# power.net
KiCad netlist of a schematic drawn in Altium Designer
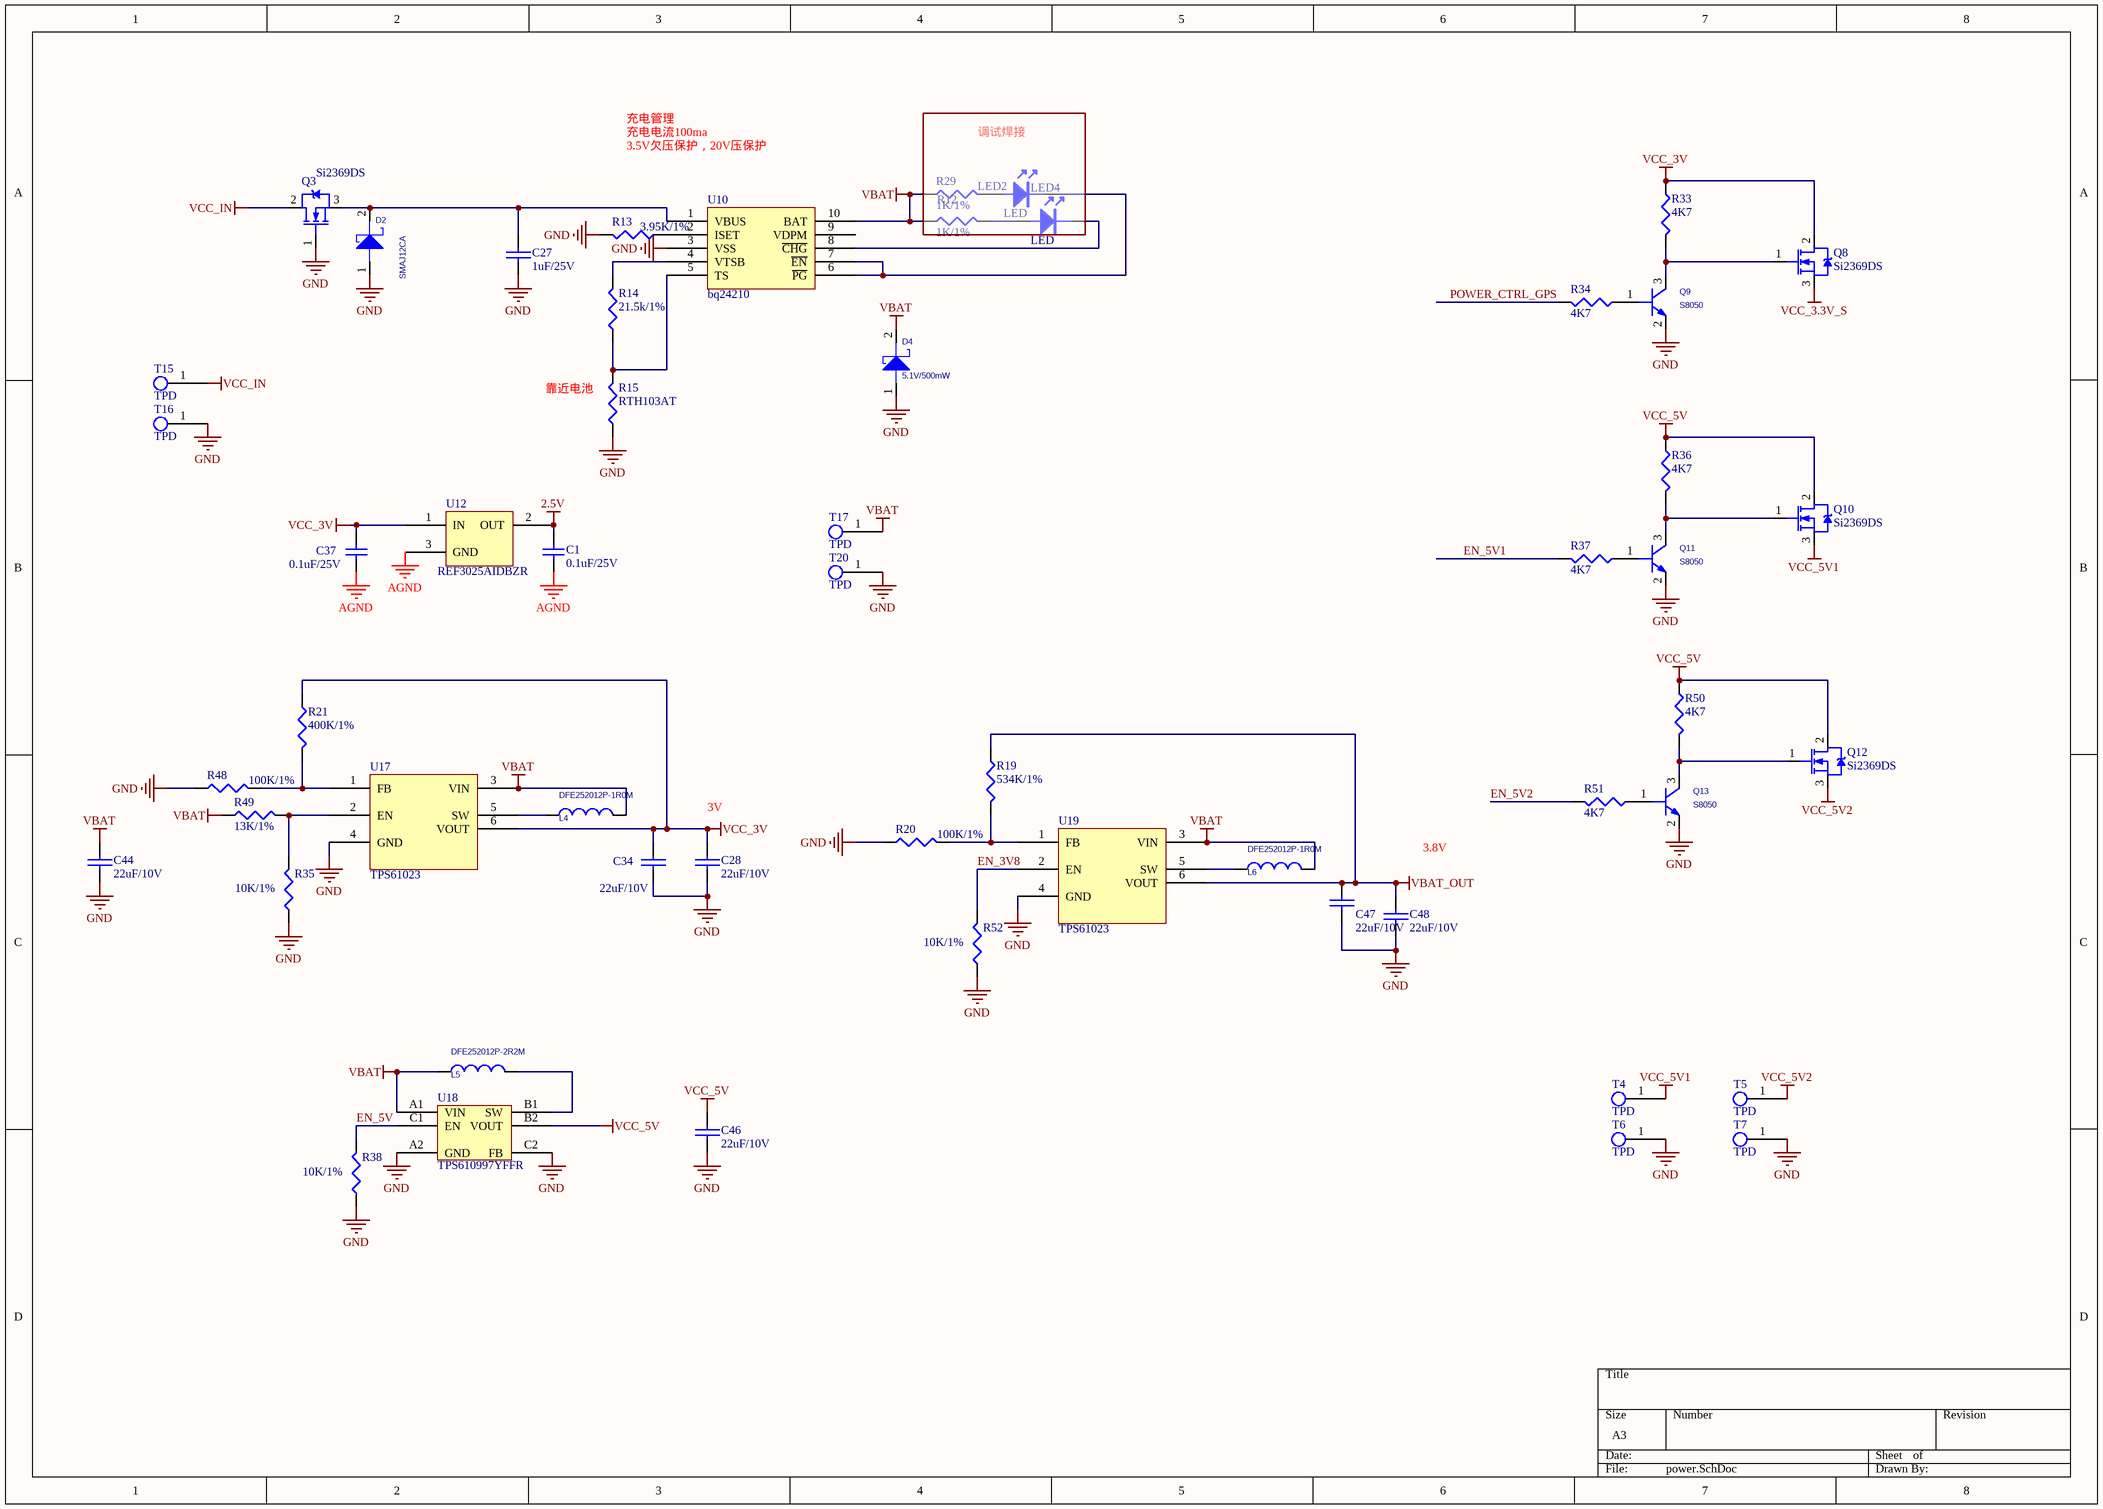
[diagram p0: power.SchDoc]

(export (version "E")
  (design (tool "Eeschema 10.0.6"))
  (components
    (comp (ref "C1")
      (value "0.1uF/25V")
      (footprint "0402c")
      (description "Capacitor")
      (fields (field (name "PUBLISHER") "Altium Limited"))
      (libsource (lib "Miscellaneous Devices") (part "Cap"))
    )
    (comp (ref "C27")
      (value "1uF/25V")
      (footprint "0402C")
      (description "Capacitor")
      (libsource (lib "ZWLIntegrated_Library") (part "CAP"))
    )
    (comp (ref "C28")
      (value "22uF/10V")
      (footprint "0805C")
      (description "Capacitor")
      (libsource (lib "ZWLIntegrated_Library") (part "CAP"))
    )
    (comp (ref "C34")
      (value "22uF/10V")
      (footprint "0805C")
      (description "Capacitor")
      (libsource (lib "ZWLIntegrated_Library") (part "CAP"))
    )
    (comp (ref "C37")
      (value "0.1uF/25V")
      (footprint "0402c")
      (description "Capacitor")
      (fields (field (name "PUBLISHER") "Altium Limited"))
      (libsource (lib "Miscellaneous Devices") (part "Cap"))
    )
    (comp (ref "C44")
      (value "22uF/10V")
      (footprint "0805C")
      (description "Capacitor")
      (libsource (lib "ZWLIntegrated_Library") (part "CAP"))
    )
    (comp (ref "C46")
      (value "22uF/10V")
      (footprint "0805C")
      (description "Capacitor")
      (libsource (lib "ZWLIntegrated_Library") (part "CAP"))
    )
    (comp (ref "C47")
      (value "22uF/10V")
      (footprint "0805C")
      (description "Capacitor")
      (libsource (lib "ZWLIntegrated_Library") (part "CAP"))
    )
    (comp (ref "C48")
      (value "22uF/10V")
      (footprint "0805C")
      (description "Capacitor")
      (libsource (lib "ZWLIntegrated_Library") (part "CAP"))
    )
    (comp (ref "D2")
      (value "SMAJ12CA")
      (footprint "SMA")
      (libsource (lib "KT_iBeacon") (part "DIODE_SCHOTTKY_0"))
    )
    (comp (ref "D4")
      (value "5.1V/500mW")
      (footprint "LL-34(D1206)")
      (fields (field (name "Comment") "DIODE_SCHOTTKY_0"))
      (libsource (lib "KT_iBeacon") (part "DIODE_SCHOTTKY_0"))
    )
    (comp (ref "L4") (value "DFE252012P-1R0M") (footprint "L2520") (libsource (lib "*") (part "INDUCTOR_1")))
    (comp (ref "L5") (value "DFE252012P-2R2M") (footprint "L2520") (libsource (lib "*") (part "INDUCTOR_1")))
    (comp (ref "L6") (value "DFE252012P-1R0M") (footprint "L2520") (libsource (lib "*") (part "INDUCTOR_1")))
    (comp (ref "LED2") (value "LED") (footprint "0603LED") (libsource (lib "我的元件库") (part "LED")))
    (comp (ref "LED4") (value "LED") (footprint "0603LED") (libsource (lib "我的元件库") (part "LED")))
    (comp (ref "Q3")
      (value "Si2369DS")
      (footprint "sot23-3")
      (description "NMOSFET")
      (libsource (lib "SM") (part "NCE4060K"))
    )
    (comp (ref "Q8")
      (value "Si2369DS")
      (footprint "sot23-3")
      (description "NMOSFET")
      (libsource (lib "SM") (part "NCE4060K"))
    )
    (comp (ref "Q9") (value "S8050") (footprint "SOT23-3") (libsource (lib "*") (part "2N1069_1")))
    (comp (ref "Q10")
      (value "Si2369DS")
      (footprint "sot23-3")
      (description "NMOSFET")
      (libsource (lib "SM") (part "NCE4060K"))
    )
    (comp (ref "Q11") (value "S8050") (footprint "SOT23-3") (libsource (lib "*") (part "2N1069_1")))
    (comp (ref "Q12")
      (value "Si2369DS")
      (footprint "sot23-3")
      (description "NMOSFET")
      (libsource (lib "SM") (part "NCE4060K"))
    )
    (comp (ref "Q13") (value "S8050") (footprint "SOT23-3") (libsource (lib "*") (part "2N1069_1")))
    (comp (ref "R12")
      (value "1K/1%")
      (footprint "0402R")
      (libsource (lib "ZWLIntegrated_Library") (part "RES1"))
    )
    (comp (ref "R13")
      (value "3.95K/1%")
      (footprint "0402R")
      (libsource (lib "ZWLIntegrated_Library") (part "RES1"))
    )
    (comp (ref "R14")
      (value "21.5k/1%")
      (footprint "0402R")
      (libsource (lib "ZWLIntegrated_Library") (part "RES1"))
    )
    (comp (ref "R15")
      (value "RTH103AT")
      (footprint "0603R")
      (libsource (lib "ZWLIntegrated_Library") (part "RES1"))
    )
    (comp (ref "R19")
      (value "534K/1%")
      (footprint "0402R")
      (libsource (lib "ZWLIntegrated_Library") (part "RES1"))
    )
    (comp (ref "R20")
      (value "100K/1%")
      (footprint "0402R")
      (libsource (lib "ZWLIntegrated_Library") (part "RES1"))
    )
    (comp (ref "R21")
      (value "400K/1%")
      (footprint "0402R")
      (libsource (lib "ZWLIntegrated_Library") (part "RES1"))
    )
    (comp (ref "R29")
      (value "1K/1%")
      (footprint "0402R")
      (libsource (lib "ZWLIntegrated_Library") (part "RES1"))
    )
    (comp (ref "R33")
      (value "4K7")
      (footprint "0402R")
      (libsource (lib "ZWLIntegrated_Library") (part "RES1"))
    )
    (comp (ref "R34")
      (value "4K7")
      (footprint "0402R")
      (libsource (lib "ZWLIntegrated_Library") (part "RES1"))
    )
    (comp (ref "R35")
      (value "10K/1%")
      (footprint "0402R")
      (libsource (lib "ZWLIntegrated_Library") (part "RES1"))
    )
    (comp (ref "R36")
      (value "4K7")
      (footprint "0402R")
      (libsource (lib "ZWLIntegrated_Library") (part "RES1"))
    )
    (comp (ref "R37")
      (value "4K7")
      (footprint "0402R")
      (libsource (lib "ZWLIntegrated_Library") (part "RES1"))
    )
    (comp (ref "R38")
      (value "10K/1%")
      (footprint "0402R")
      (libsource (lib "ZWLIntegrated_Library") (part "RES1"))
    )
    (comp (ref "R48")
      (value "100K/1%")
      (footprint "0402R")
      (libsource (lib "ZWLIntegrated_Library") (part "RES1"))
    )
    (comp (ref "R49")
      (value "13K/1%")
      (footprint "0402R")
      (libsource (lib "ZWLIntegrated_Library") (part "RES1"))
    )
    (comp (ref "R50")
      (value "4K7")
      (footprint "0402R")
      (libsource (lib "ZWLIntegrated_Library") (part "RES1"))
    )
    (comp (ref "R51")
      (value "4K7")
      (footprint "0402R")
      (libsource (lib "ZWLIntegrated_Library") (part "RES1"))
    )
    (comp (ref "R52")
      (value "10K/1%")
      (footprint "0402R")
      (libsource (lib "ZWLIntegrated_Library") (part "RES1"))
    )
    (comp (ref "T4") (value "TPD") (footprint "Pcblib_20110825:TP") (libsource (lib "stm32") (part "TPD")))
    (comp (ref "T5") (value "TPD") (footprint "Pcblib_20110825:TP") (libsource (lib "stm32") (part "TPD")))
    (comp (ref "T6") (value "TPD") (footprint "Pcblib_20110825:TP") (libsource (lib "stm32") (part "TPD")))
    (comp (ref "T7") (value "TPD") (footprint "Pcblib_20110825:TP") (libsource (lib "stm32") (part "TPD")))
    (comp (ref "T15") (value "TPD") (footprint "Pcblib_20110825:TP") (libsource (lib "stm32") (part "TPD")))
    (comp (ref "T16") (value "TPD") (footprint "Pcblib_20110825:TP") (libsource (lib "stm32") (part "TPD")))
    (comp (ref "T17") (value "TPD") (footprint "Pcblib_20110825:TP") (libsource (lib "stm32") (part "TPD")))
    (comp (ref "T20") (value "TPD") (footprint "Pcblib_20110825:TP") (libsource (lib "stm32") (part "TPD")))
    (comp (ref "U10")
      (value "bq24210")
      (footprint "QFN50P200X300X80-10N")
      (libsource (lib "stm32") (part "bq2410"))
    )
    (comp (ref "U12")
      (value "REF3025AIDBZR")
      (footprint "SOT23-3")
      (libsource (lib "Schlib1") (part "REF3012"))
    )
    (comp (ref "U17") (value "TPS61023") (footprint "SOT563-6") (libsource (lib "stm32") (part "TPS61023")))
    (comp (ref "U18")
      (value "TPS610997YFFR")
      (footprint "TPS610997YFFR")
      (libsource (lib "stm32") (part "TPS610997YFFR"))
    )
    (comp (ref "U19") (value "TPS61023") (footprint "SOT563-6") (libsource (lib "stm32") (part "TPS61023")))
  )
  (nets
    (net (code "1") (name "/EN_3V8") (class "Default")
      (node (ref "R52") (pin "2") (pinfunction "2_2") (pintype "passive"))
      (node (ref "U19") (pin "2") (pinfunction "EN_2") (pintype "passive"))
    )
    (net (code "2") (name "/EN_5V") (class "Default")
      (node (ref "R38") (pin "2") (pinfunction "2_2") (pintype "passive"))
      (node (ref "U18") (pin "C1") (pinfunction "EN_C1") (pintype "passive"))
    )
    (net (code "3") (name "/EN_5V1") (class "Default")
      (node (ref "R37") (pin "2") (pinfunction "2_2") (pintype "passive"))
    )
    (net (code "4") (name "/EN_5V2") (class "Default")
      (node (ref "R51") (pin "2") (pinfunction "2_2") (pintype "passive"))
    )
    (net (code "5") (name "/POWER_CTRL_GPS") (class "Default")
      (node (ref "R34") (pin "2") (pinfunction "2_2") (pintype "passive"))
    )
    (net (code "6") (name "2.5V") (class "Default")
      (node (ref "C1") (pin "1") (pinfunction "1_1") (pintype "passive"))
      (node (ref "U12") (pin "2") (pinfunction "OUT_2") (pintype "passive"))
    )
    (net (code "7") (name "AGND") (class "Default")
      (node (ref "C1") (pin "2") (pinfunction "2_2") (pintype "passive"))
      (node (ref "C37") (pin "2") (pinfunction "2_2") (pintype "passive"))
      (node (ref "U12") (pin "3") (pinfunction "GND_3") (pintype "passive"))
    )
    (net (code "8") (name "GND") (class "Default")
      (node (ref "C27") (pin "2") (pinfunction "2_2") (pintype "passive"))
      (node (ref "C28") (pin "2") (pinfunction "2_2") (pintype "passive"))
      (node (ref "C34") (pin "2") (pinfunction "2_2") (pintype "passive"))
      (node (ref "C44") (pin "2") (pinfunction "2_2") (pintype "passive"))
      (node (ref "C46") (pin "2") (pinfunction "2_2") (pintype "passive"))
      (node (ref "C47") (pin "2") (pinfunction "2_2") (pintype "passive"))
      (node (ref "C48") (pin "2") (pinfunction "2_2") (pintype "passive"))
      (node (ref "D2") (pin "1") (pinfunction "1_1") (pintype "passive"))
      (node (ref "D4") (pin "1") (pinfunction "1_1") (pintype "passive"))
      (node (ref "Q11") (pin "2") (pinfunction "E_2") (pintype "passive"))
      (node (ref "Q13") (pin "2") (pinfunction "E_2") (pintype "passive"))
      (node (ref "Q3") (pin "1") (pinfunction "G_1") (pintype "passive"))
      (node (ref "Q9") (pin "2") (pinfunction "E_2") (pintype "passive"))
      (node (ref "R13") (pin "2") (pinfunction "2_2") (pintype "passive"))
      (node (ref "R15") (pin "1") (pinfunction "1_1") (pintype "passive"))
      (node (ref "R20") (pin "1") (pinfunction "1_1") (pintype "passive"))
      (node (ref "R35") (pin "1") (pinfunction "1_1") (pintype "passive"))
      (node (ref "R38") (pin "1") (pinfunction "1_1") (pintype "passive"))
      (node (ref "R48") (pin "1") (pinfunction "1_1") (pintype "passive"))
      (node (ref "R52") (pin "1") (pinfunction "1_1") (pintype "passive"))
      (node (ref "T16") (pin "1") (pintype "passive"))
      (node (ref "T20") (pin "1") (pintype "passive"))
      (node (ref "T6") (pin "1") (pintype "passive"))
      (node (ref "T7") (pin "1") (pintype "passive"))
      (node (ref "U10") (pin "3") (pinfunction "VSS_3") (pintype "passive"))
      (node (ref "U17") (pin "4") (pinfunction "GND_4") (pintype "passive"))
      (node (ref "U18") (pin "A2") (pinfunction "GND_A2") (pintype "passive"))
      (node (ref "U18") (pin "C2") (pinfunction "FB_C2") (pintype "passive"))
      (node (ref "U19") (pin "4") (pinfunction "GND_4") (pintype "passive"))
    )
    (net (code "9") (name "Net-(LED2-Pad1)") (class "Default")
      (node (ref "LED2") (pin "1") (pinfunction "1_1") (pintype "passive"))
      (node (ref "R29") (pin "2") (pinfunction "2_2") (pintype "passive"))
    )
    (net (code "10") (name "Net-(LED4-Pad1)") (class "Default")
      (node (ref "LED4") (pin "1") (pinfunction "1_1") (pintype "passive"))
      (node (ref "R12") (pin "2") (pinfunction "2_2") (pintype "passive"))
    )
    (net (code "11") (name "Net-(Q3-S)") (class "Default")
      (node (ref "C27") (pin "1") (pinfunction "1_1") (pintype "passive"))
      (node (ref "D2") (pin "2") (pinfunction "2_2") (pintype "passive"))
      (node (ref "Q3") (pin "3") (pinfunction "S_3") (pintype "passive"))
      (node (ref "U10") (pin "1") (pinfunction "VBUS_1") (pintype "passive"))
    )
    (net (code "12") (name "Net-(Q8-G)") (class "Default")
      (node (ref "Q8") (pin "1") (pinfunction "G_1") (pintype "passive"))
      (node (ref "Q9") (pin "3") (pinfunction "C_3") (pintype "passive"))
      (node (ref "R33") (pin "2") (pinfunction "2_2") (pintype "passive"))
    )
    (net (code "13") (name "Net-(Q9-B)") (class "Default")
      (node (ref "Q9") (pin "1") (pinfunction "B_1") (pintype "passive"))
      (node (ref "R34") (pin "1") (pinfunction "1_1") (pintype "passive"))
    )
    (net (code "14") (name "Net-(Q10-G)") (class "Default")
      (node (ref "Q10") (pin "1") (pinfunction "G_1") (pintype "passive"))
      (node (ref "Q11") (pin "3") (pinfunction "C_3") (pintype "passive"))
      (node (ref "R36") (pin "2") (pinfunction "2_2") (pintype "passive"))
    )
    (net (code "15") (name "Net-(Q11-B)") (class "Default")
      (node (ref "Q11") (pin "1") (pinfunction "B_1") (pintype "passive"))
      (node (ref "R37") (pin "1") (pinfunction "1_1") (pintype "passive"))
    )
    (net (code "16") (name "Net-(Q12-G)") (class "Default")
      (node (ref "Q12") (pin "1") (pinfunction "G_1") (pintype "passive"))
      (node (ref "Q13") (pin "3") (pinfunction "C_3") (pintype "passive"))
      (node (ref "R50") (pin "2") (pinfunction "2_2") (pintype "passive"))
    )
    (net (code "17") (name "Net-(Q13-B)") (class "Default")
      (node (ref "Q13") (pin "1") (pinfunction "B_1") (pintype "passive"))
      (node (ref "R51") (pin "1") (pinfunction "1_1") (pintype "passive"))
    )
    (net (code "18") (name "Net-(U10-ISET)") (class "Default")
      (node (ref "R13") (pin "1") (pinfunction "1_1") (pintype "passive"))
      (node (ref "U10") (pin "2") (pinfunction "ISET_2") (pintype "passive"))
    )
    (net (code "19") (name "Net-(U10-TS)") (class "Default")
      (node (ref "R14") (pin "1") (pinfunction "1_1") (pintype "passive"))
      (node (ref "R15") (pin "2") (pinfunction "2_2") (pintype "passive"))
      (node (ref "U10") (pin "5") (pinfunction "TS_5") (pintype "passive"))
    )
    (net (code "20") (name "Net-(U10-VTSB)") (class "Default")
      (node (ref "R14") (pin "2") (pinfunction "2_2") (pintype "passive"))
      (node (ref "U10") (pin "4") (pinfunction "VTSB_4") (pintype "passive"))
    )
    (net (code "21") (name "Net-(U10-~{CHG})") (class "Default")
      (node (ref "LED4") (pin "2") (pinfunction "2_2") (pintype "passive"))
      (node (ref "U10") (pin "8") (pinfunction "~{CHG}_8") (pintype "passive"))
    )
    (net (code "22") (name "Net-(U10-~{EN})") (class "Default")
      (node (ref "LED2") (pin "2") (pinfunction "2_2") (pintype "passive"))
      (node (ref "U10") (pin "6") (pinfunction "~{PG}_6") (pintype "passive"))
      (node (ref "U10") (pin "7") (pinfunction "~{EN}_7") (pintype "passive"))
    )
    (net (code "23") (name "Net-(U17-EN)") (class "Default")
      (node (ref "R35") (pin "2") (pinfunction "2_2") (pintype "passive"))
      (node (ref "R49") (pin "2") (pinfunction "2_2") (pintype "passive"))
      (node (ref "U17") (pin "2") (pinfunction "EN_2") (pintype "passive"))
    )
    (net (code "24") (name "Net-(U17-FB)") (class "Default")
      (node (ref "R21") (pin "2") (pinfunction "2_2") (pintype "passive"))
      (node (ref "R48") (pin "2") (pinfunction "2_2") (pintype "passive"))
      (node (ref "U17") (pin "1") (pinfunction "FB_1") (pintype "passive"))
    )
    (net (code "25") (name "Net-(U17-SW)") (class "Default")
      (node (ref "L4") (pin "1") (pinfunction "1_1") (pintype "passive"))
      (node (ref "U17") (pin "5") (pinfunction "SW_5") (pintype "passive"))
    )
    (net (code "26") (name "Net-(U18-SW)") (class "Default")
      (node (ref "L5") (pin "2") (pinfunction "2_2") (pintype "passive"))
      (node (ref "U18") (pin "B1") (pinfunction "SW_B1") (pintype "passive"))
    )
    (net (code "27") (name "Net-(U19-FB)") (class "Default")
      (node (ref "R19") (pin "2") (pinfunction "2_2") (pintype "passive"))
      (node (ref "R20") (pin "2") (pinfunction "2_2") (pintype "passive"))
      (node (ref "U19") (pin "1") (pinfunction "FB_1") (pintype "passive"))
    )
    (net (code "28") (name "Net-(U19-SW)") (class "Default")
      (node (ref "L6") (pin "1") (pinfunction "1_1") (pintype "passive"))
      (node (ref "U19") (pin "5") (pinfunction "SW_5") (pintype "passive"))
    )
    (net (code "29") (name "VBAT") (class "Default")
      (node (ref "C44") (pin "1") (pinfunction "1_1") (pintype "passive"))
      (node (ref "D4") (pin "2") (pinfunction "2_2") (pintype "passive"))
      (node (ref "L4") (pin "2") (pinfunction "2_2") (pintype "passive"))
      (node (ref "L5") (pin "1") (pinfunction "1_1") (pintype "passive"))
      (node (ref "L6") (pin "2") (pinfunction "2_2") (pintype "passive"))
      (node (ref "R12") (pin "1") (pinfunction "1_1") (pintype "passive"))
      (node (ref "R29") (pin "1") (pinfunction "1_1") (pintype "passive"))
      (node (ref "R49") (pin "1") (pinfunction "1_1") (pintype "passive"))
      (node (ref "T17") (pin "1") (pintype "passive"))
      (node (ref "U10") (pin "10") (pinfunction "BAT_10") (pintype "passive"))
      (node (ref "U17") (pin "3") (pinfunction "VIN_3") (pintype "passive"))
      (node (ref "U18") (pin "A1") (pinfunction "VIN_A1") (pintype "passive"))
      (node (ref "U19") (pin "3") (pinfunction "VIN_3") (pintype "passive"))
    )
    (net (code "30") (name "VBAT_OUT") (class "Default")
      (node (ref "C47") (pin "1") (pinfunction "1_1") (pintype "passive"))
      (node (ref "C48") (pin "1") (pinfunction "1_1") (pintype "passive"))
      (node (ref "R19") (pin "1") (pinfunction "1_1") (pintype "passive"))
      (node (ref "U19") (pin "6") (pinfunction "VOUT_6") (pintype "passive"))
    )
    (net (code "31") (name "VCC_3.3V_S") (class "Default")
      (node (ref "Q8") (pin "3") (pinfunction "S_3") (pintype "passive"))
    )
    (net (code "32") (name "VCC_3V") (class "Default")
      (node (ref "C28") (pin "1") (pinfunction "1_1") (pintype "passive"))
      (node (ref "C34") (pin "1") (pinfunction "1_1") (pintype "passive"))
      (node (ref "C37") (pin "1") (pinfunction "1_1") (pintype "passive"))
      (node (ref "Q8") (pin "2") (pinfunction "D_2") (pintype "passive"))
      (node (ref "R21") (pin "1") (pinfunction "1_1") (pintype "passive"))
      (node (ref "R33") (pin "1") (pinfunction "1_1") (pintype "passive"))
      (node (ref "U12") (pin "1") (pinfunction "IN_1") (pintype "passive"))
      (node (ref "U17") (pin "6") (pinfunction "VOUT_6") (pintype "passive"))
    )
    (net (code "33") (name "VCC_5V") (class "Default")
      (node (ref "C46") (pin "1") (pinfunction "1_1") (pintype "passive"))
      (node (ref "Q10") (pin "2") (pinfunction "D_2") (pintype "passive"))
      (node (ref "Q12") (pin "2") (pinfunction "D_2") (pintype "passive"))
      (node (ref "R36") (pin "1") (pinfunction "1_1") (pintype "passive"))
      (node (ref "R50") (pin "1") (pinfunction "1_1") (pintype "passive"))
      (node (ref "U18") (pin "B2") (pinfunction "VOUT_B2") (pintype "passive"))
    )
    (net (code "34") (name "VCC_5V1") (class "Default")
      (node (ref "Q10") (pin "3") (pinfunction "S_3") (pintype "passive"))
      (node (ref "T4") (pin "1") (pintype "passive"))
    )
    (net (code "35") (name "VCC_5V2") (class "Default")
      (node (ref "Q12") (pin "3") (pinfunction "S_3") (pintype "passive"))
      (node (ref "T5") (pin "1") (pintype "passive"))
    )
    (net (code "36") (name "VCC_IN") (class "Default")
      (node (ref "Q3") (pin "2") (pinfunction "D_2") (pintype "passive"))
      (node (ref "T15") (pin "1") (pintype "passive"))
    )
    (net (code "37") (name "unconnected-(U10-VDPM-Pad9)") (class "Default")
      (node (ref "U10") (pin "9") (pinfunction "VDPM_9") (pintype "passive"))
    )
  )
)
